# 99_Mark_Hole_Heatsink.net
KiCad netlist of a schematic drawn in Altium Designer
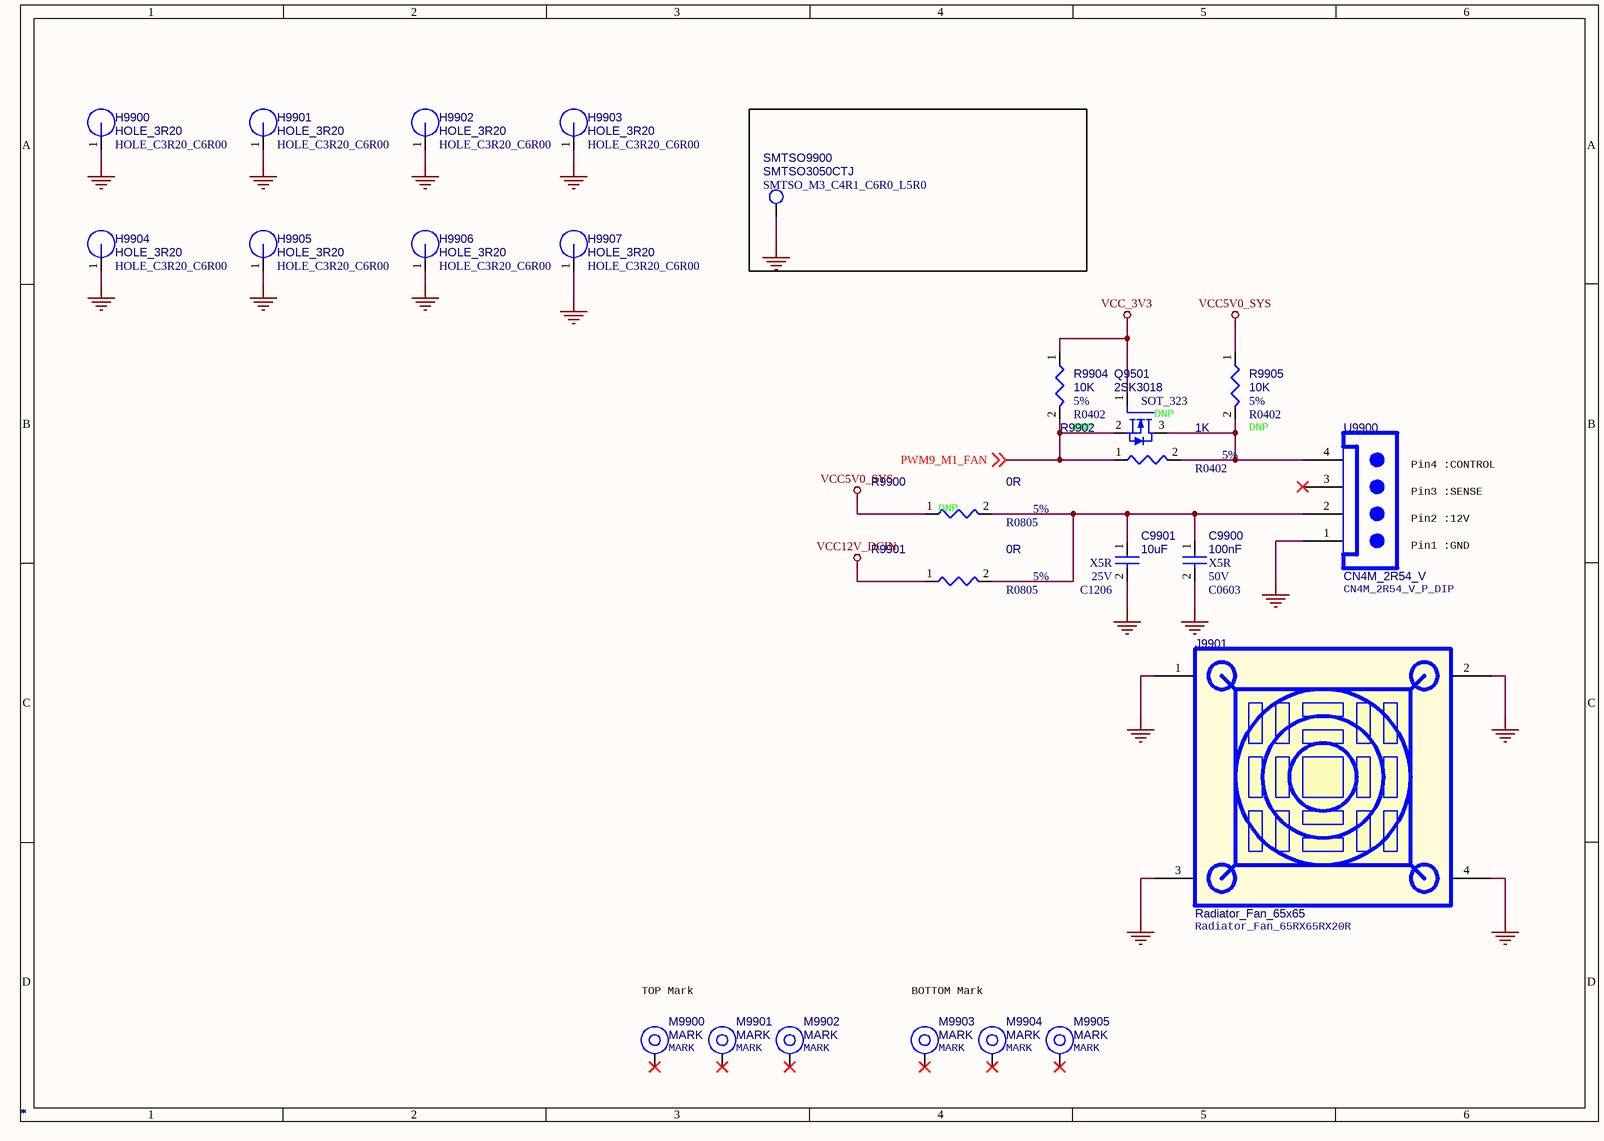
[diagram p0: 99.Mark_Hole_Heatsink.SchDoc]

(export (version "E")
  (design (tool "Eeschema 10.0.6"))
  (components
    (comp (ref "C9900")
      (value "*")
      (footprint "C0603")
      (description "cap,100.00nF,+/-10%,50V,X5R,C0603")
      (fields
        (field (name "VOLTAGE") "50V")
        (field (name "PCB FOOTPRINT") "C0603")
        (field (name "DIELECTRIC") "X5R")
        (field (name "TOLERANCE") "10%")
        (field (name "MANUFACTURER") "TDK")
        (field (name "ALTIUM_UNNAMED_1") "100nF")
        (field (name "CREATED BY") "JJJ")
      )
      (libsource (lib "*") (part "CAP NP"))
    )
    (comp (ref "C9901")
      (value "*")
      (footprint "C1206")
      (description "cap,10.00uF,+/-10%,25V,X5R,C1206")
      (fields
        (field (name "VOLTAGE") "25V")
        (field (name "PCB FOOTPRINT") "C1206")
        (field (name "DIELECTRIC") "X5R")
        (field (name "MANUFACTURER") "TDK")
        (field (name "TOLERANCE") "10%")
        (field (name "ALTIUM_UNNAMED_1") "10uF")
        (field (name "CREATED BY") "JJJ")
      )
      (libsource (lib "*") (part "CAP NP"))
    )
    (comp (ref "H9900")
      (value "*")
      (footprint "H3.8MM")
      (description "Ц±ѕ¶3.2mmВЭЛїїЧ,ОЮН­Цщ")
      (fields
        (field (name "PCB FOOTPRINT") "HOLE_C3R20_C6R00")
        (field (name "ALTIUM_UNNAMED_1") "HOLE_3R20")
        (field (name "CREATED BY") "YWQ")
      )
      (libsource (lib "*") (part "Hole"))
    )
    (comp (ref "H9901")
      (value "*")
      (footprint "H3.8MM")
      (description "Ц±ѕ¶3.2mmВЭЛїїЧ,ОЮН­Цщ")
      (fields
        (field (name "PCB FOOTPRINT") "HOLE_C3R20_C6R00")
        (field (name "ALTIUM_UNNAMED_1") "HOLE_3R20")
        (field (name "CREATED BY") "YWQ")
      )
      (libsource (lib "*") (part "Hole"))
    )
    (comp (ref "H9902")
      (value "*")
      (footprint "H3.8MM")
      (description "Ц±ѕ¶3.2mmВЭЛїїЧ,ОЮН­Цщ")
      (fields
        (field (name "PCB FOOTPRINT") "HOLE_C3R20_C6R00")
        (field (name "ALTIUM_UNNAMED_1") "HOLE_3R20")
        (field (name "CREATED BY") "YWQ")
      )
      (libsource (lib "*") (part "Hole"))
    )
    (comp (ref "H9903")
      (value "*")
      (footprint "H3.8MM")
      (description "Ц±ѕ¶3.2mmВЭЛїїЧ,ОЮН­Цщ")
      (fields
        (field (name "PCB FOOTPRINT") "HOLE_C3R20_C6R00")
        (field (name "ALTIUM_UNNAMED_1") "HOLE_3R20")
        (field (name "CREATED BY") "YWQ")
      )
      (libsource (lib "*") (part "Hole"))
    )
    (comp (ref "H9904")
      (value "*")
      (footprint "H3.8MM")
      (description "Ц±ѕ¶3.2mmВЭЛїїЧ,ОЮН­Цщ")
      (fields
        (field (name "PCB FOOTPRINT") "HOLE_C3R20_C6R00")
        (field (name "ALTIUM_UNNAMED_1") "HOLE_3R20")
        (field (name "CREATED BY") "YWQ")
      )
      (libsource (lib "*") (part "Hole"))
    )
    (comp (ref "H9905")
      (value "*")
      (footprint "H3.8MM")
      (description "Ц±ѕ¶3.2mmВЭЛїїЧ,ОЮН­Цщ")
      (fields
        (field (name "PCB FOOTPRINT") "HOLE_C3R20_C6R00")
        (field (name "ALTIUM_UNNAMED_1") "HOLE_3R20")
        (field (name "CREATED BY") "YWQ")
      )
      (libsource (lib "*") (part "Hole"))
    )
    (comp (ref "H9906")
      (value "*")
      (footprint "H3.8MM")
      (description "Ц±ѕ¶3.2mmВЭЛїїЧ,ОЮН­Цщ")
      (fields
        (field (name "PCB FOOTPRINT") "HOLE_C3R20_C6R00")
        (field (name "ALTIUM_UNNAMED_1") "HOLE_3R20")
        (field (name "CREATED BY") "YWQ")
      )
      (libsource (lib "*") (part "Hole"))
    )
    (comp (ref "H9907")
      (value "*")
      (footprint "H3.8MM")
      (description "Ц±ѕ¶3.2mmВЭЛїїЧ,ОЮН­Цщ")
      (fields
        (field (name "PCB FOOTPRINT") "HOLE_C3R20_C6R00")
        (field (name "ALTIUM_UNNAMED_1") "HOLE_3R20")
        (field (name "CREATED BY") "YWQ")
      )
      (libsource (lib "*") (part "Hole"))
    )
    (comp (ref "J9901")
      (value "*")
      (footprint "Radiator_Fan_65RX65RX20R")
      (fields
        (field (name "PCB FOOTPRINT") "Radiator_Fan_65RX65RX20R")
        (field (name "ALTIUM_UNNAMED_1") "Radiator_Fan_65x65")
      )
      (libsource (lib "*") (part "Radiator_Fan_2"))
    )
    (comp (ref "M9900")
      (value "*")
      (footprint "MARK")
      (description "MARK Symble")
      (fields
        (field (name "PCB FOOTPRINT") "MARK")
        (field (name "ALTIUM_UNNAMED_1") "MARK")
        (field (name "CREATED BY") "JJJ")
      )
      (libsource (lib "*") (part "MARK"))
    )
    (comp (ref "M9901")
      (value "*")
      (footprint "MARK")
      (description "MARK Symble")
      (fields
        (field (name "PCB FOOTPRINT") "MARK")
        (field (name "ALTIUM_UNNAMED_1") "MARK")
        (field (name "CREATED BY") "JJJ")
      )
      (libsource (lib "*") (part "MARK"))
    )
    (comp (ref "M9902")
      (value "*")
      (footprint "MARK")
      (description "MARK Symble")
      (fields
        (field (name "PCB FOOTPRINT") "MARK")
        (field (name "ALTIUM_UNNAMED_1") "MARK")
        (field (name "CREATED BY") "JJJ")
      )
      (libsource (lib "*") (part "MARK"))
    )
    (comp (ref "M9903")
      (value "*")
      (footprint "MARK")
      (description "MARK Symble")
      (fields
        (field (name "PCB FOOTPRINT") "MARK")
        (field (name "ALTIUM_UNNAMED_1") "MARK")
        (field (name "CREATED BY") "JJJ")
      )
      (libsource (lib "*") (part "MARK"))
    )
    (comp (ref "M9904")
      (value "*")
      (footprint "MARK")
      (description "MARK Symble")
      (fields
        (field (name "PCB FOOTPRINT") "MARK")
        (field (name "ALTIUM_UNNAMED_1") "MARK")
        (field (name "CREATED BY") "JJJ")
      )
      (libsource (lib "*") (part "MARK"))
    )
    (comp (ref "M9905")
      (value "*")
      (footprint "MARK")
      (description "MARK Symble")
      (fields
        (field (name "PCB FOOTPRINT") "MARK")
        (field (name "ALTIUM_UNNAMED_1") "MARK")
        (field (name "CREATED BY") "JJJ")
      )
      (libsource (lib "*") (part "MARK"))
    )
    (comp (ref "Q9501")
      (value "*")
      (footprint "SOT23")
      (description "NMOS,2SK3018,SOT_323,Id=0.1A,Vds=30V")
      (fields
        (field (name "PCB FOOTPRINT") "SOT_323")
        (field (name "OPTION") "DNP")
        (field (name "MANUFACTURER") "ROHM")
        (field (name "ALTIUM_UNNAMED_1") "2SK3018")
        (field (name "CREATED BY") "JJJ")
      )
      (libsource (lib "*") (part "MOSFET N"))
    )
    (comp (ref "R9900")
      (value "*")
      (footprint "R0402")
      (description "НЁУГєсД¤µзЧи,0R,+/-5%,R0805,1/8W.")
      (fields
        (field (name "PCB FOOTPRINT") "R0805")
        (field (name "TOLERANCE") "5%")
        (field (name "MANUFACTURER") "YAGEO")
        (field (name "OPTION") "DNP")
        (field (name "ALTIUM_UNNAMED_1") "0R")
        (field (name "CREATED BY") "YTL")
      )
      (libsource (lib "*") (part "RESISTOR_Dup1"))
    )
    (comp (ref "R9901")
      (value "*")
      (footprint "R0402")
      (description "НЁУГєсД¤µзЧи,0R,+/-5%,R0805,1/8W.")
      (fields
        (field (name "PCB FOOTPRINT") "R0805")
        (field (name "TOLERANCE") "5%")
        (field (name "MANUFACTURER") "YAGEO")
        (field (name "ALTIUM_UNNAMED_1") "0R")
        (field (name "CREATED BY") "YTL")
      )
      (libsource (lib "*") (part "RESISTOR_Dup1"))
    )
    (comp (ref "R9902")
      (value "*")
      (footprint "R0402")
      (description "НЁУГєсД¤µзЧи,1K,+/-5%,R0402,1/16W.")
      (fields
        (field (name "PCB FOOTPRINT") "R0402")
        (field (name "TOLERANCE") "5%")
        (field (name "MANUFACTURER") "YAGEO")
        (field (name "ALTIUM_UNNAMED_1") "1K")
        (field (name "CREATED BY") "YTL")
      )
      (libsource (lib "*") (part "RESISTOR_Dup1"))
    )
    (comp (ref "R9904")
      (value "*")
      (footprint "R0402")
      (description "НЁУГєсД¤µзЧи,10K,+/-5%,R0402,1/16W.")
      (fields
        (field (name "PCB FOOTPRINT") "R0402")
        (field (name "TOLERANCE") "5%")
        (field (name "OPTION") "DNP")
        (field (name "MANUFACTURER") "YAGEO")
        (field (name "ALTIUM_UNNAMED_1") "10K")
        (field (name "CREATED BY") "YTL")
      )
      (libsource (lib "*") (part "RESISTOR_Dup1"))
    )
    (comp (ref "R9905")
      (value "*")
      (footprint "R0402")
      (description "НЁУГєсД¤µзЧи,10K,+/-5%,R0402,1/16W.")
      (fields
        (field (name "PCB FOOTPRINT") "R0402")
        (field (name "TOLERANCE") "5%")
        (field (name "OPTION") "DNP")
        (field (name "MANUFACTURER") "YAGEO")
        (field (name "ALTIUM_UNNAMED_1") "10K")
        (field (name "CREATED BY") "YTL")
      )
      (libsource (lib "*") (part "RESISTOR_Dup1"))
    )
    (comp (ref "SMTSO9900")
      (value "*")
      (footprint "TEST")
      (description "єёЅУВЭДёM3,ёЯ¶И5mmЈ»")
      (fields
        (field (name "PCB FOOTPRINT") "SMTSO_M3_C4R1_C6R0_L5R0")
        (field (name "ALTIUM_UNNAMED_1") "SMTSO3050CTJ")
        (field (name "CREATED BY") "JJJ")
      )
      (libsource (lib "*") (part "SMTSO"))
    )
    (comp (ref "U9900")
      (value "*")
      (footprint "CN4M_2R54_V_P_DIP")
      (fields
        (field (name "PCB FOOTPRINT") "CN4M_2R54_V_P_DIP")
        (field (name "ALTIUM_UNNAMED_1") "CN4M_2R54_V")
      )
      (libsource (lib "*") (part "CON4_0"))
    )
  )
  (nets
    (net (code "1") (name "GND") (class "Default")
      (node (ref "C9900") (pin "2") (pinfunction "2_2") (pintype "passive"))
      (node (ref "C9901") (pin "2") (pinfunction "2_2") (pintype "passive"))
      (node (ref "H9900") (pin "1") (pinfunction "1_1") (pintype "passive"))
      (node (ref "H9901") (pin "1") (pinfunction "1_1") (pintype "passive"))
      (node (ref "H9902") (pin "1") (pinfunction "1_1") (pintype "passive"))
      (node (ref "H9903") (pin "1") (pinfunction "1_1") (pintype "passive"))
      (node (ref "H9904") (pin "1") (pinfunction "1_1") (pintype "passive"))
      (node (ref "H9905") (pin "1") (pinfunction "1_1") (pintype "passive"))
      (node (ref "H9906") (pin "1") (pinfunction "1_1") (pintype "passive"))
      (node (ref "H9907") (pin "1") (pinfunction "1_1") (pintype "passive"))
      (node (ref "J9901") (pin "1") (pinfunction "1_1") (pintype "passive"))
      (node (ref "J9901") (pin "2") (pinfunction "2_2") (pintype "passive"))
      (node (ref "J9901") (pin "3") (pinfunction "3_3") (pintype "passive"))
      (node (ref "J9901") (pin "4") (pinfunction "4_4") (pintype "passive"))
      (node (ref "SMTSO9900") (pin "1") (pinfunction "1_1") (pintype "passive"))
      (node (ref "U9900") (pin "1") (pinfunction "GND_1") (pintype "passive"))
    )
    (net (code "2") (name "Net-(Q9501-DRAIN)") (class "Default")
      (node (ref "Q9501") (pin "3") (pinfunction "DRAIN_3") (pintype "passive"))
      (node (ref "R9902") (pin "2") (pinfunction "2_2") (pintype "passive"))
      (node (ref "R9905") (pin "2") (pinfunction "2_2") (pintype "passive"))
      (node (ref "U9900") (pin "4") (pinfunction "3V3_4") (pintype "passive"))
    )
    (net (code "3") (name "Net-(U9900-RX)") (class "Default")
      (node (ref "C9900") (pin "1") (pinfunction "1_1") (pintype "passive"))
      (node (ref "C9901") (pin "1") (pinfunction "1_1") (pintype "passive"))
      (node (ref "R9900") (pin "2") (pinfunction "2_2") (pintype "passive"))
      (node (ref "R9901") (pin "2") (pinfunction "2_2") (pintype "passive"))
      (node (ref "U9900") (pin "2") (pinfunction "RX_2") (pintype "passive"))
    )
    (net (code "4") (name "PWM9_M1_FAN") (class "Default")
      (node (ref "Q9501") (pin "2") (pinfunction "SOURCE_2") (pintype "passive"))
      (node (ref "R9902") (pin "1") (pinfunction "1_1") (pintype "passive"))
      (node (ref "R9904") (pin "2") (pinfunction "2_2") (pintype "passive"))
    )
    (net (code "5") (name "VCC5V0_SYS") (class "Default")
      (node (ref "R9900") (pin "1") (pinfunction "1_1") (pintype "passive"))
      (node (ref "R9905") (pin "1") (pinfunction "1_1") (pintype "passive"))
    )
    (net (code "6") (name "VCC12V_DCIN") (class "Default")
      (node (ref "R9901") (pin "1") (pinfunction "1_1") (pintype "passive"))
    )
    (net (code "7") (name "VCC_3V3") (class "Default")
      (node (ref "Q9501") (pin "1") (pinfunction "GATE_1") (pintype "passive"))
      (node (ref "R9904") (pin "1") (pinfunction "1_1") (pintype "passive"))
    )
    (net (code "8") (name "unconnected-(M9900-Pad1)") (class "Default")
      (node (ref "M9900") (pin "1") (pinfunction "1_1") (pintype "passive+no_connect"))
    )
    (net (code "9") (name "unconnected-(M9901-Pad1)") (class "Default")
      (node (ref "M9901") (pin "1") (pinfunction "1_1") (pintype "passive+no_connect"))
    )
    (net (code "10") (name "unconnected-(M9902-Pad1)") (class "Default")
      (node (ref "M9902") (pin "1") (pinfunction "1_1") (pintype "passive+no_connect"))
    )
    (net (code "11") (name "unconnected-(M9903-Pad1)") (class "Default")
      (node (ref "M9903") (pin "1") (pinfunction "1_1") (pintype "passive+no_connect"))
    )
    (net (code "12") (name "unconnected-(M9904-Pad1)") (class "Default")
      (node (ref "M9904") (pin "1") (pinfunction "1_1") (pintype "passive+no_connect"))
    )
    (net (code "13") (name "unconnected-(M9905-Pad1)") (class "Default")
      (node (ref "M9905") (pin "1") (pinfunction "1_1") (pintype "passive+no_connect"))
    )
    (net (code "14") (name "unconnected-(U9900-TX-Pad3)") (class "Default")
      (node (ref "U9900") (pin "3") (pinfunction "TX_3") (pintype "passive+no_connect"))
    )
  )
)
